# PDOC.net
KiCad netlist of a schematic drawn in Altium Designer
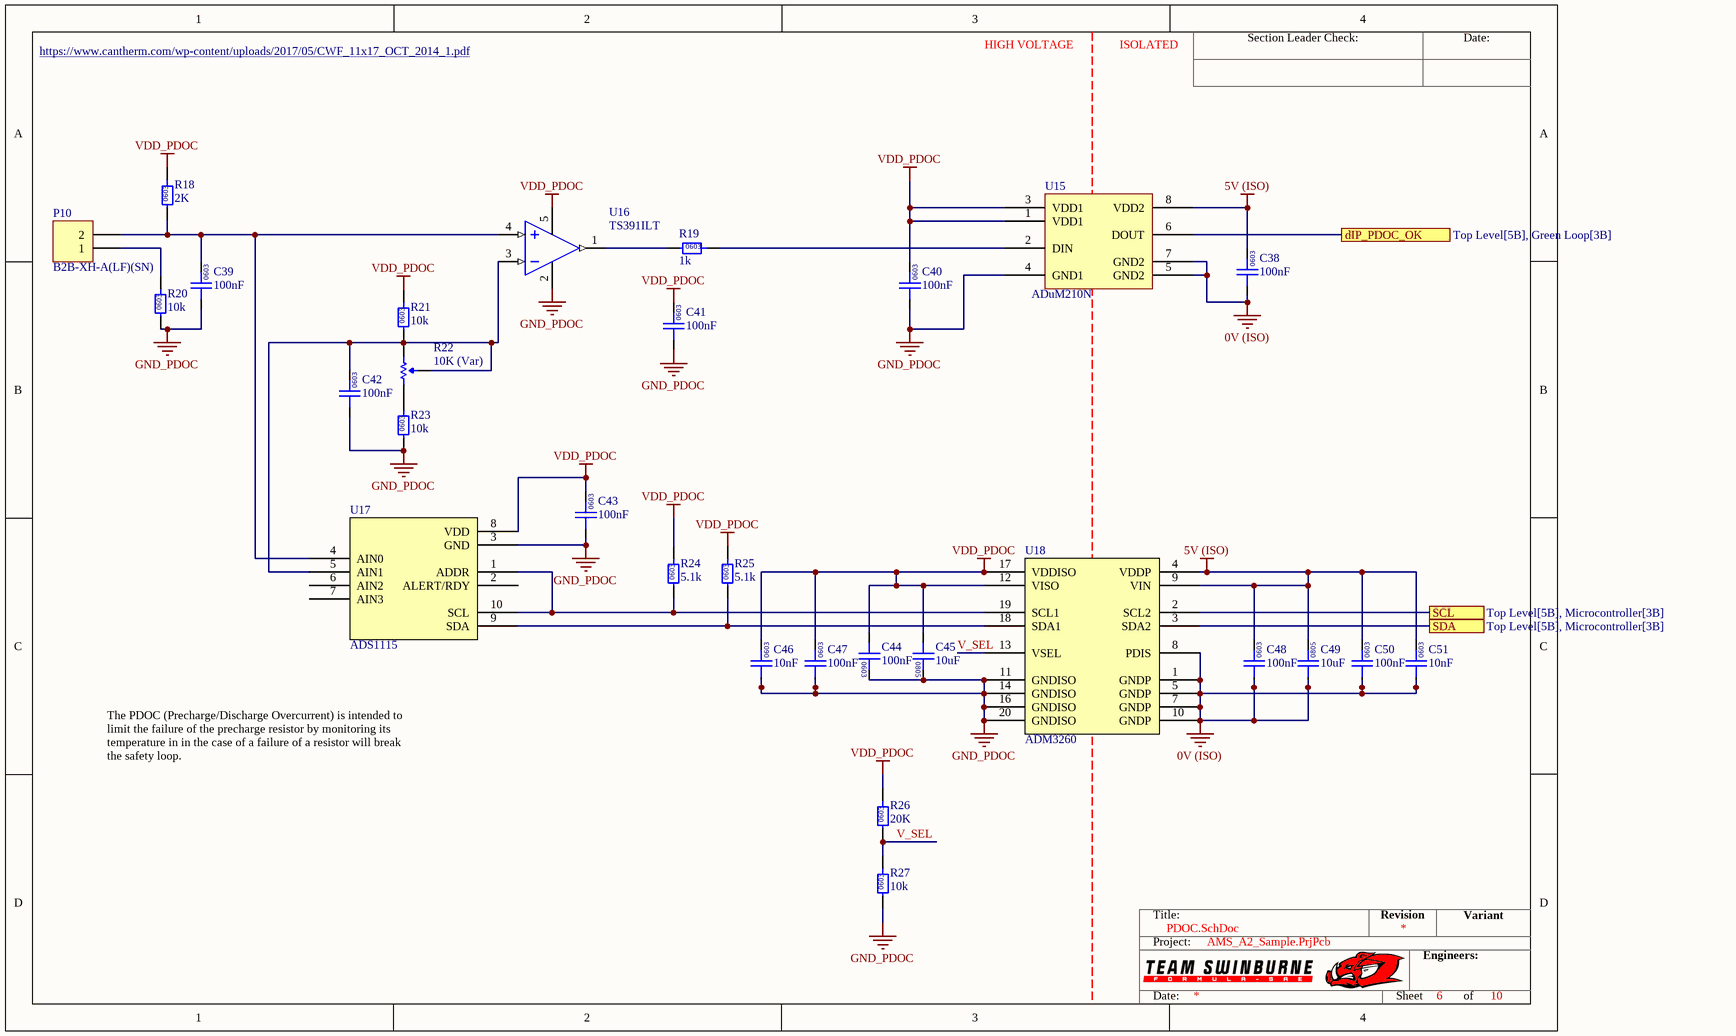
[diagram p0: PDOC.SchDoc]

(export (version "E")
  (design (tool "Eeschema 10.0.6"))
  (components
    (comp (ref "C38")
      (value "100nF")
      (footprint "0603")
      (fields
        (field (name "PART NUMBER") "GCM188L81H104KA57D")
        (field (name "MANUFACTURER") "muRata")
        (field (name "TOLERANCE") "±10%")
      )
      (libsource (lib "ts_standard_library") (part "Capacitor 0603"))
    )
    (comp (ref "C39")
      (value "100nF")
      (footprint "0603")
      (fields
        (field (name "PART NUMBER") "GCM188L81H104KA57D")
        (field (name "MANUFACTURER") "muRata")
        (field (name "TOLERANCE") "±10%")
      )
      (libsource (lib "ts_standard_library") (part "Capacitor 0603"))
    )
    (comp (ref "C40")
      (value "100nF")
      (footprint "0603")
      (fields
        (field (name "PART NUMBER") "GCM188L81H104KA57D")
        (field (name "MANUFACTURER") "muRata")
        (field (name "TOLERANCE") "±10%")
      )
      (libsource (lib "ts_standard_library") (part "Capacitor 0603"))
    )
    (comp (ref "C41")
      (value "100nF")
      (footprint "0603")
      (fields
        (field (name "PART NUMBER") "GCM188L81H104KA57D")
        (field (name "MANUFACTURER") "muRata")
        (field (name "TOLERANCE") "±10%")
      )
      (libsource (lib "ts_standard_library") (part "Capacitor 0603"))
    )
    (comp (ref "C42")
      (value "100nF")
      (footprint "0603")
      (fields
        (field (name "PART NUMBER") "GCM188L81H104KA57D")
        (field (name "MANUFACTURER") "muRata")
        (field (name "TOLERANCE") "±10%")
      )
      (libsource (lib "ts_standard_library") (part "Capacitor 0603"))
    )
    (comp (ref "C43")
      (value "100nF")
      (footprint "0603")
      (fields
        (field (name "PART NUMBER") "GCM188L81H104KA57D")
        (field (name "MANUFACTURER") "muRata")
        (field (name "TOLERANCE") "±10%")
      )
      (libsource (lib "ts_standard_library") (part "Capacitor 0603"))
    )
    (comp (ref "C44")
      (value "100nF")
      (footprint "0603")
      (fields
        (field (name "PART NUMBER") "GCM188L81H104KA57D")
        (field (name "MANUFACTURER") "muRata")
        (field (name "TOLERANCE") "±10%")
      )
      (libsource (lib "ts_standard_library") (part "Capacitor 0603"))
    )
    (comp (ref "C45")
      (value "10uF")
      (footprint "0805")
      (fields
        (field (name "PART NUMBER") "GRM21BR6YA106KE43L")
        (field (name "MANUFACTURER") "muRata")
        (field (name "TOLERANCE") "10%")
      )
      (libsource (lib "ts_standard_library") (part "Capacitor 0805"))
    )
    (comp (ref "C46")
      (value "10nF")
      (footprint "0603")
      (fields
        (field (name "PART NUMBER") "GCM188L81H103KA03D")
        (field (name "MANUFACTURER") "muRata")
        (field (name "TOLERANCE") "±10%")
      )
      (libsource (lib "ts_standard_library") (part "Capacitor 0603"))
    )
    (comp (ref "C47")
      (value "100nF")
      (footprint "0603")
      (fields
        (field (name "PART NUMBER") "GCM188L81H104KA57D")
        (field (name "MANUFACTURER") "muRata")
        (field (name "TOLERANCE") "±10%")
      )
      (libsource (lib "ts_standard_library") (part "Capacitor 0603"))
    )
    (comp (ref "C48")
      (value "100nF")
      (footprint "0603")
      (fields
        (field (name "PART NUMBER") "GCM188L81H104KA57D")
        (field (name "MANUFACTURER") "muRata")
        (field (name "TOLERANCE") "±10%")
      )
      (libsource (lib "ts_standard_library") (part "Capacitor 0603"))
    )
    (comp (ref "C49")
      (value "10uF")
      (footprint "0805")
      (fields
        (field (name "PART NUMBER") "GRM21BR6YA106KE43L")
        (field (name "MANUFACTURER") "muRata")
        (field (name "TOLERANCE") "10%")
      )
      (libsource (lib "ts_standard_library") (part "Capacitor 0805"))
    )
    (comp (ref "C50")
      (value "100nF")
      (footprint "0603")
      (fields
        (field (name "PART NUMBER") "GCM188L81H104KA57D")
        (field (name "MANUFACTURER") "muRata")
        (field (name "TOLERANCE") "±10%")
      )
      (libsource (lib "ts_standard_library") (part "Capacitor 0603"))
    )
    (comp (ref "C51")
      (value "10nF")
      (footprint "0603")
      (fields
        (field (name "PART NUMBER") "GCM188L81H103KA03D")
        (field (name "MANUFACTURER") "muRata")
        (field (name "TOLERANCE") "±10%")
      )
      (libsource (lib "ts_standard_library") (part "Capacitor 0603"))
    )
    (comp (ref "P10")
      (value "B2B-XH-A(LF)(SN)")
      (footprint "XH 2 PIN VERT")
      (fields (field (name "DIGIKEY PART NUMBER") "455-2247-ND") (field (name "CONTACT") "Tin"))
      (libsource (lib "ts_standard_connectors") (part "Header 1x2"))
    )
    (comp (ref "R18")
      (value "2K")
      (footprint "0603")
      (fields
        (field (name "PART NUMBER") "RC0603FR-072KL")
        (field (name "MANUFACTURER") "YAGEO")
        (field (name "TOLERANCE") "0.01")
      )
      (libsource (lib "ts_standard_library") (part "Resistor 0603"))
    )
    (comp (ref "R19")
      (value "1k")
      (footprint "0603")
      (fields
        (field (name "PART NUMBER") "RC0603FR-071KL")
        (field (name "MANUFACTURER") "YAGEO")
        (field (name "TOLERANCE") "0.01")
      )
      (libsource (lib "ts_standard_library") (part "Resistor 0603"))
    )
    (comp (ref "R20")
      (value "10k")
      (footprint "0603")
      (fields
        (field (name "PART NUMBER") "RC0603FR-0710KL")
        (field (name "MANUFACTURER") "YAGEO")
        (field (name "TOLERANCE") "0.01")
      )
      (libsource (lib "ts_standard_library") (part "Resistor 0603"))
    )
    (comp (ref "R21")
      (value "10k")
      (footprint "0603")
      (fields
        (field (name "PART NUMBER") "RC0603FR-0710KL")
        (field (name "MANUFACTURER") "YAGEO")
        (field (name "TOLERANCE") "0.01")
      )
      (libsource (lib "ts_standard_library") (part "Resistor 0603"))
    )
    (comp (ref "R22")
      (value "10K (Var)")
      (footprint "B 3296")
      (fields
        (field (name "PART NUMBER") "3296W-1-103LF")
        (field (name "MANUFACTURER") "Bournes Inc")
        (field (name "TOLERANCE") "0.1")
      )
      (libsource (lib "ts_standard_library") (part "Resistor (Potentiometer)"))
    )
    (comp (ref "R23")
      (value "10k")
      (footprint "0603")
      (fields
        (field (name "PART NUMBER") "RC0603FR-0710KL")
        (field (name "MANUFACTURER") "YAGEO")
        (field (name "TOLERANCE") "0.01")
      )
      (libsource (lib "ts_standard_library") (part "Resistor 0603"))
    )
    (comp (ref "R24")
      (value "5.1k")
      (footprint "0603")
      (fields
        (field (name "PART NUMBER") "RC0603JR-075K1L")
        (field (name "MANUFACTURER") "YAGEO")
        (field (name "TOLERANCE") "0.01")
      )
      (libsource (lib "ts_standard_library") (part "Resistor 0603"))
    )
    (comp (ref "R25")
      (value "5.1k")
      (footprint "0603")
      (fields
        (field (name "PART NUMBER") "RC0603JR-075K1L")
        (field (name "MANUFACTURER") "YAGEO")
        (field (name "TOLERANCE") "0.01")
      )
      (libsource (lib "ts_standard_library") (part "Resistor 0603"))
    )
    (comp (ref "R26")
      (value "20K")
      (footprint "0603")
      (fields
        (field (name "PART NUMBER") "RC0603FR-0720KL")
        (field (name "MANUFACTURER") "YAGEO")
        (field (name "TOLERANCE") "0.01")
      )
      (libsource (lib "ts_standard_library") (part "Resistor 0603"))
    )
    (comp (ref "R27")
      (value "10k")
      (footprint "0603")
      (fields
        (field (name "PART NUMBER") "RC0603FR-0710KL")
        (field (name "MANUFACTURER") "YAGEO")
        (field (name "TOLERANCE") "0.01")
      )
      (libsource (lib "ts_standard_library") (part "Resistor 0603"))
    )
    (comp (ref "U15")
      (value "ADuM210N")
      (footprint "SOIC-8W")
      (description "DIGITAL ISOLATOR, SINGLE CHANNEL")
      (libsource (lib "Team Swinburne") (part "ADuM210N"))
    )
    (comp (ref "U16")
      (value "TS391ILT")
      (footprint "ON SOT-23-5")
      (description "IC COMP LO PWR SGL V SOT 23-5L")
      (libsource (lib "Team Swinburne") (part "TS391ILT"))
    )
    (comp (ref "U17")
      (value "ADS1115")
      (footprint "TI 10-VSSOP")
      (description "16 Bit Analog to Digital Converter 2, 4 Input 1 Sigma-Delta 10-VSSOP")
      (fields
        (field (name "MANUFACTURER") "Texas Instruments")
        (field (name "DIGIKEY PART NUMBER") "296-38849-1-ND")
      )
      (libsource (lib "ts_standard_library") (part "ADS1115"))
    )
    (comp (ref "U18")
      (value "ADM3260")
      (footprint "AD 20-SSOP")
      (description "I²C Digital Isolator 2500Vrms 2 Channel 25kV/µs CMTI 20-SSOP (0.209\", 5.30mm Width)")
      (libsource (lib "Team Swinburne") (part "ADM3260"))
    )
  )
  (nets
    (net (code "1") (name "/SCL") (class "Default")
      (node (ref "U18") (pin "2") (pinfunction "SCL2_2") (pintype "passive"))
    )
    (net (code "2") (name "/SDA") (class "Default")
      (node (ref "U18") (pin "3") (pinfunction "SDA2_3") (pintype "passive"))
    )
    (net (code "3") (name "/V_SEL") (class "Default")
      (node (ref "R26") (pin "1") (pinfunction "1_1") (pintype "passive"))
      (node (ref "R27") (pin "2") (pinfunction "2_2") (pintype "passive"))
      (node (ref "U18") (pin "13") (pinfunction "VSEL_13") (pintype "passive"))
    )
    (net (code "4") (name "/dIP_PDOC_OK") (class "Default")
      (node (ref "U15") (pin "6") (pinfunction "DOUT_6") (pintype "passive"))
    )
    (net (code "5") (name "0V (ISO)") (class "Default")
      (node (ref "C38") (pin "1") (pinfunction "1_1") (pintype "passive"))
      (node (ref "C48") (pin "1") (pinfunction "1_1") (pintype "passive"))
      (node (ref "C49") (pin "1") (pinfunction "1_1") (pintype "passive"))
      (node (ref "C50") (pin "1") (pinfunction "1_1") (pintype "passive"))
      (node (ref "C51") (pin "1") (pinfunction "1_1") (pintype "passive"))
      (node (ref "U15") (pin "5") (pinfunction "GND2_5") (pintype "passive"))
      (node (ref "U15") (pin "7") (pinfunction "GND2_7") (pintype "passive"))
      (node (ref "U18") (pin "1") (pinfunction "GNDP_1") (pintype "passive"))
      (node (ref "U18") (pin "10") (pinfunction "GNDP_10") (pintype "passive"))
      (node (ref "U18") (pin "5") (pinfunction "GNDP_5") (pintype "passive"))
      (node (ref "U18") (pin "7") (pinfunction "GNDP_7") (pintype "passive"))
      (node (ref "U18") (pin "8") (pinfunction "PDIS_8") (pintype "passive"))
    )
    (net (code "6") (name "5V (ISO)") (class "Default")
      (node (ref "C38") (pin "2") (pinfunction "2_2") (pintype "passive"))
      (node (ref "C48") (pin "2") (pinfunction "2_2") (pintype "passive"))
      (node (ref "C49") (pin "2") (pinfunction "2_2") (pintype "passive"))
      (node (ref "C50") (pin "2") (pinfunction "2_2") (pintype "passive"))
      (node (ref "C51") (pin "2") (pinfunction "2_2") (pintype "passive"))
      (node (ref "U15") (pin "8") (pinfunction "VDD2_8") (pintype "passive"))
      (node (ref "U18") (pin "4") (pinfunction "VDDP_4") (pintype "passive"))
      (node (ref "U18") (pin "9") (pinfunction "VIN_9") (pintype "passive"))
    )
    (net (code "7") (name "GND_PDOC") (class "Default")
      (node (ref "C39") (pin "1") (pinfunction "1_1") (pintype "passive"))
      (node (ref "C40") (pin "1") (pinfunction "1_1") (pintype "passive"))
      (node (ref "C41") (pin "1") (pinfunction "1_1") (pintype "passive"))
      (node (ref "C42") (pin "1") (pinfunction "1_1") (pintype "passive"))
      (node (ref "C43") (pin "1") (pinfunction "1_1") (pintype "passive"))
      (node (ref "C44") (pin "2") (pinfunction "2_2") (pintype "passive"))
      (node (ref "C45") (pin "2") (pinfunction "2_2") (pintype "passive"))
      (node (ref "C46") (pin "1") (pinfunction "1_1") (pintype "passive"))
      (node (ref "C47") (pin "1") (pinfunction "1_1") (pintype "passive"))
      (node (ref "R20") (pin "1") (pinfunction "1_1") (pintype "passive"))
      (node (ref "R23") (pin "1") (pinfunction "1_1") (pintype "passive"))
      (node (ref "R27") (pin "1") (pinfunction "1_1") (pintype "passive"))
      (node (ref "U15") (pin "4") (pinfunction "GND1_4") (pintype "passive"))
      (node (ref "U16") (pin "2") (pinfunction "VCC-_2") (pintype "power_in"))
      (node (ref "U17") (pin "3") (pinfunction "GND_3") (pintype "passive"))
      (node (ref "U18") (pin "11") (pinfunction "GNDISO_11") (pintype "passive"))
      (node (ref "U18") (pin "14") (pinfunction "GNDISO_14") (pintype "passive"))
      (node (ref "U18") (pin "16") (pinfunction "GNDISO_16") (pintype "passive"))
      (node (ref "U18") (pin "20") (pinfunction "GNDISO_20") (pintype "passive"))
    )
    (net (code "8") (name "Net-(P10-Pad1)") (class "Default")
      (node (ref "P10") (pin "1") (pinfunction "1_1") (pintype "passive"))
      (node (ref "R20") (pin "2") (pinfunction "2_2") (pintype "passive"))
    )
    (net (code "9") (name "Net-(R22-CCW)") (class "Default")
      (node (ref "C42") (pin "2") (pinfunction "2_2") (pintype "passive"))
      (node (ref "R21") (pin "1") (pinfunction "1_1") (pintype "passive"))
      (node (ref "R22") (pin "1") (pinfunction "CCW_1") (pintype "passive"))
      (node (ref "R22") (pin "2") (pinfunction "Wiper_2") (pintype "passive"))
      (node (ref "U16") (pin "3") (pinfunction "IN-_3") (pintype "input"))
      (node (ref "U17") (pin "5") (pinfunction "AIN1_5") (pintype "passive"))
    )
    (net (code "10") (name "Net-(R22-CW)") (class "Default")
      (node (ref "R22") (pin "3") (pinfunction "CW_3") (pintype "passive"))
      (node (ref "R23") (pin "2") (pinfunction "2_2") (pintype "passive"))
    )
    (net (code "11") (name "Net-(U15-DIN)") (class "Default")
      (node (ref "R19") (pin "2") (pinfunction "2_2") (pintype "passive"))
      (node (ref "U15") (pin "2") (pinfunction "DIN_2") (pintype "passive"))
    )
    (net (code "12") (name "Net-(U16-IIN+)") (class "Default")
      (node (ref "C39") (pin "2") (pinfunction "2_2") (pintype "passive"))
      (node (ref "P10") (pin "2") (pinfunction "2_2") (pintype "passive"))
      (node (ref "R18") (pin "1") (pinfunction "1_1") (pintype "passive"))
      (node (ref "U16") (pin "4") (pinfunction "IIN+_4") (pintype "input"))
      (node (ref "U17") (pin "4") (pinfunction "AIN0_4") (pintype "passive"))
    )
    (net (code "13") (name "Net-(U16-OUT)") (class "Default")
      (node (ref "R19") (pin "1") (pinfunction "1_1") (pintype "passive"))
      (node (ref "U16") (pin "1") (pinfunction "OUT_1") (pintype "output"))
    )
    (net (code "14") (name "Net-(U17-ADDR)") (class "Default")
      (node (ref "R24") (pin "1") (pinfunction "1_1") (pintype "passive"))
      (node (ref "U17") (pin "1") (pinfunction "ADDR_1") (pintype "passive"))
      (node (ref "U17") (pin "10") (pinfunction "SCL_10") (pintype "passive"))
      (node (ref "U18") (pin "19") (pinfunction "SCL1_19") (pintype "passive"))
    )
    (net (code "15") (name "Net-(U17-SDA)") (class "Default")
      (node (ref "R25") (pin "1") (pinfunction "1_1") (pintype "passive"))
      (node (ref "U17") (pin "9") (pinfunction "SDA_9") (pintype "passive"))
      (node (ref "U18") (pin "18") (pinfunction "SDA1_18") (pintype "passive"))
    )
    (net (code "16") (name "VDD_PDOC") (class "Default")
      (node (ref "C40") (pin "2") (pinfunction "2_2") (pintype "passive"))
      (node (ref "C41") (pin "2") (pinfunction "2_2") (pintype "passive"))
      (node (ref "C43") (pin "2") (pinfunction "2_2") (pintype "passive"))
      (node (ref "C44") (pin "1") (pinfunction "1_1") (pintype "passive"))
      (node (ref "C45") (pin "1") (pinfunction "1_1") (pintype "passive"))
      (node (ref "C46") (pin "2") (pinfunction "2_2") (pintype "passive"))
      (node (ref "C47") (pin "2") (pinfunction "2_2") (pintype "passive"))
      (node (ref "R18") (pin "2") (pinfunction "2_2") (pintype "passive"))
      (node (ref "R21") (pin "2") (pinfunction "2_2") (pintype "passive"))
      (node (ref "R24") (pin "2") (pinfunction "2_2") (pintype "passive"))
      (node (ref "R25") (pin "2") (pinfunction "2_2") (pintype "passive"))
      (node (ref "R26") (pin "2") (pinfunction "2_2") (pintype "passive"))
      (node (ref "U15") (pin "1") (pinfunction "VDD1_1") (pintype "passive"))
      (node (ref "U15") (pin "3") (pinfunction "VDD1_3") (pintype "passive"))
      (node (ref "U16") (pin "5") (pinfunction "VCC+_5") (pintype "power_in"))
      (node (ref "U17") (pin "8") (pinfunction "VDD_8") (pintype "passive"))
      (node (ref "U18") (pin "12") (pinfunction "VISO_12") (pintype "passive"))
      (node (ref "U18") (pin "17") (pinfunction "VDDISO_17") (pintype "passive"))
    )
    (net (code "17") (name "unconnected-(U17-AIN2-Pad6)") (class "Default")
      (node (ref "U17") (pin "6") (pinfunction "AIN2_6") (pintype "passive"))
    )
    (net (code "18") (name "unconnected-(U17-AIN3-Pad7)") (class "Default")
      (node (ref "U17") (pin "7") (pinfunction "AIN3_7") (pintype "passive"))
    )
    (net (code "19") (name "unconnected-(U17-ALERT{slash}RDY-Pad2)") (class "Default")
      (node (ref "U17") (pin "2") (pinfunction "ALERT/RDY_2") (pintype "passive"))
    )
  )
)
